# schematic.net
KiCad netlist of a schematic drawn in Altium Designer
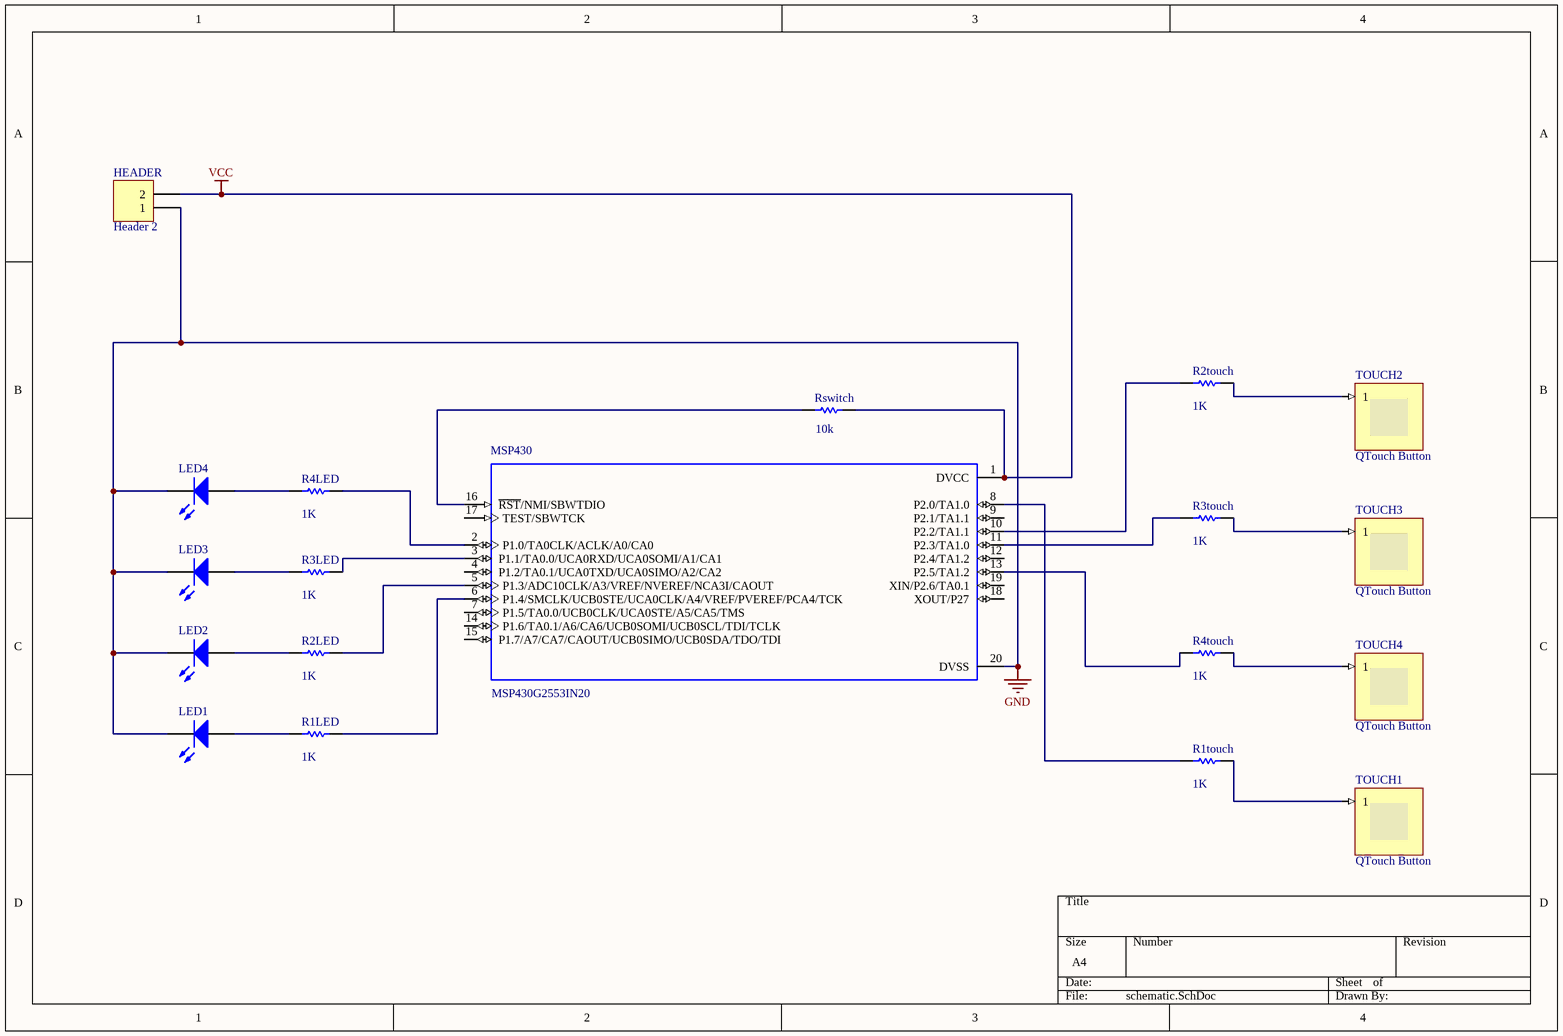
[diagram p0: schematic.SchDoc]

(export (version "E")
  (design (tool "Eeschema 10.0.6"))
  (components
    (comp (ref "HEADER")
      (value "Header 2")
      (footprint "HDR1X2")
      (description "Header, 2-Pin")
      (fields (field (name "PUBLISHER") "Altium Limited"))
      (libsource (lib "Miscellaneous Connectors") (part "Header 2"))
    )
    (comp (ref "LED1")
      (value "LED4")
      (footprint "LED-0")
      (description "Typical INFRARED GaAs LED")
      (fields (field (name "PUBLISHER") "Altium Limited"))
      (libsource (lib "Miscellaneous Devices") (part "LED0"))
    )
    (comp (ref "LED2")
      (value "LED3")
      (footprint "LED-0")
      (description "Typical INFRARED GaAs LED")
      (fields (field (name "PUBLISHER") "Altium Limited"))
      (libsource (lib "Miscellaneous Devices") (part "LED0"))
    )
    (comp (ref "LED3")
      (value "LED2")
      (footprint "LED-0")
      (description "Typical INFRARED GaAs LED")
      (fields (field (name "PUBLISHER") "Altium Limited"))
      (libsource (lib "Miscellaneous Devices") (part "LED0"))
    )
    (comp (ref "LED4")
      (value "LED1")
      (footprint "LED-0")
      (description "Typical INFRARED GaAs LED")
      (fields (field (name "PUBLISHER") "Altium Limited"))
      (libsource (lib "Miscellaneous Devices") (part "LED0"))
    )
    (comp (ref "MSP430")
      (value "MSP430G2553IN20")
      (footprint "*DIP794W45P254L2692H508Q20")
      (description "MSP430G2x53, MSP430G2x13 Mixed Signal Microcontroller 20-PDIP -40 to 85")
      (fields (field (name "MF") "Texas Instruments"))
      (libsource (lib "MSP430G2553IN20") (part "MSP430G2553IN20"))
    )
    (comp (ref "R1LED")
      (value "1K")
      (footprint "AXIAL-0.3")
      (description "Resistor")
      (fields (field (name "Comment") "Res1") (field (name "PUBLISHER") "Altium Limited"))
      (libsource (lib "Miscellaneous Devices") (part "Res1"))
    )
    (comp (ref "R1touch")
      (value "1K")
      (footprint "AXIAL-0.3")
      (description "Resistor")
      (fields (field (name "Comment") "Res1") (field (name "PUBLISHER") "Altium Limited"))
      (libsource (lib "Miscellaneous Devices") (part "Res1"))
    )
    (comp (ref "R2LED")
      (value "1K")
      (footprint "AXIAL-0.3")
      (description "Resistor")
      (fields (field (name "Comment") "Res1") (field (name "PUBLISHER") "Altium Limited"))
      (libsource (lib "Miscellaneous Devices") (part "Res1"))
    )
    (comp (ref "R2touch")
      (value "1K")
      (footprint "AXIAL-0.3")
      (description "Resistor")
      (fields (field (name "Comment") "Res1") (field (name "PUBLISHER") "Altium Limited"))
      (libsource (lib "Miscellaneous Devices") (part "Res1"))
    )
    (comp (ref "R3LED")
      (value "1K")
      (footprint "AXIAL-0.3")
      (description "Resistor")
      (fields (field (name "Comment") "Res1") (field (name "PUBLISHER") "Altium Limited"))
      (libsource (lib "Miscellaneous Devices") (part "Res1"))
    )
    (comp (ref "R3touch")
      (value "1K")
      (footprint "AXIAL-0.3")
      (description "Resistor")
      (fields (field (name "Comment") "Res1") (field (name "PUBLISHER") "Altium Limited"))
      (libsource (lib "Miscellaneous Devices") (part "Res1"))
    )
    (comp (ref "R4LED")
      (value "1K")
      (footprint "AXIAL-0.3")
      (description "Resistor")
      (fields (field (name "Comment") "Res1") (field (name "PUBLISHER") "Altium Limited"))
      (libsource (lib "Miscellaneous Devices") (part "Res1"))
    )
    (comp (ref "R4touch")
      (value "1K")
      (footprint "AXIAL-0.3")
      (description "Resistor")
      (fields (field (name "Comment") "Res1") (field (name "PUBLISHER") "Altium Limited"))
      (libsource (lib "Miscellaneous Devices") (part "Res1"))
    )
    (comp (ref "Rswitch")
      (value "10k")
      (footprint "AXIAL-0.3")
      (description "Resistor")
      (fields (field (name "Comment") "Rswitch") (field (name "PUBLISHER") "Altium Limited"))
      (libsource (lib "Miscellaneous Devices") (part "Res1"))
    )
    (comp (ref "TOUCH1") (value "QTouch Button") (libsource (lib "Atmel QTouch") (part "QTouchButton")))
    (comp (ref "TOUCH2") (value "QTouch Button") (libsource (lib "Atmel QTouch") (part "QTouchButton")))
    (comp (ref "TOUCH3") (value "QTouch Button") (libsource (lib "Atmel QTouch") (part "QTouchButton")))
    (comp (ref "TOUCH4") (value "QTouch Button") (libsource (lib "Atmel QTouch") (part "QTouchButton")))
  )
  (nets
    (net (code "1") (name "GND") (class "Default")
      (node (ref "HEADER") (pin "1") (pinfunction "1_1") (pintype "passive"))
      (node (ref "LED1") (pin "2") (pinfunction "K_2") (pintype "passive"))
      (node (ref "LED2") (pin "2") (pinfunction "K_2") (pintype "passive"))
      (node (ref "LED3") (pin "2") (pinfunction "K_2") (pintype "passive"))
      (node (ref "LED4") (pin "2") (pinfunction "K_2") (pintype "passive"))
      (node (ref "MSP430") (pin "20") (pinfunction "DVSS_20") (pintype "power_in"))
    )
    (net (code "2") (name "Net-(LED1-A)") (class "Default")
      (node (ref "LED1") (pin "1") (pinfunction "A_1") (pintype "passive"))
      (node (ref "R1LED") (pin "1") (pinfunction "1_1") (pintype "passive"))
    )
    (net (code "3") (name "Net-(LED2-A)") (class "Default")
      (node (ref "LED2") (pin "1") (pinfunction "A_1") (pintype "passive"))
      (node (ref "R2LED") (pin "1") (pinfunction "1_1") (pintype "passive"))
    )
    (net (code "4") (name "Net-(LED3-A)") (class "Default")
      (node (ref "LED3") (pin "1") (pinfunction "A_1") (pintype "passive"))
      (node (ref "R3LED") (pin "1") (pinfunction "1_1") (pintype "passive"))
    )
    (net (code "5") (name "Net-(LED4-A)") (class "Default")
      (node (ref "LED4") (pin "1") (pinfunction "A_1") (pintype "passive"))
      (node (ref "R4LED") (pin "1") (pinfunction "1_1") (pintype "passive"))
    )
    (net (code "6") (name "Net-(MSP430-P1.0{slash}TA0CLK{slash}ACLK{slash}A0{slash}CA0)") (class "Default")
      (node (ref "MSP430") (pin "2") (pinfunction "P1.0/TA0CLK/ACLK/A0/CA0_2") (pintype "bidirectional"))
      (node (ref "R4LED") (pin "2") (pinfunction "2_2") (pintype "passive"))
    )
    (net (code "7") (name "Net-(MSP430-P1.1{slash}TA0.0{slash}UCA0RXD{slash}UCA0SOMI{slash}A1{slash}CA1)") (class "Default")
      (node (ref "MSP430") (pin "3") (pinfunction "P1.1/TA0.0/UCA0RXD/UCA0SOMI/A1/CA1_3") (pintype "bidirectional"))
      (node (ref "R3LED") (pin "2") (pinfunction "2_2") (pintype "passive"))
    )
    (net (code "8") (name "Net-(MSP430-P1.3{slash}ADC10CLK{slash}A3{slash}VREF{slash}NVEREF{slash}NCA3I{slash}CAOUT)") (class "Default")
      (node (ref "MSP430") (pin "5") (pinfunction "P1.3/ADC10CLK/A3/VREF/NVEREF/NCA3I/CAOUT_5") (pintype "bidirectional"))
      (node (ref "R2LED") (pin "2") (pinfunction "2_2") (pintype "passive"))
    )
    (net (code "9") (name "Net-(MSP430-P1.4{slash}SMCLK{slash}UCB0STE{slash}UCA0CLK{slash}A4{slash}VREF{slash}PVEREF{slash}PCA4{slash}TCK)") (class "Default")
      (node (ref "MSP430") (pin "6") (pinfunction "P1.4/SMCLK/UCB0STE/UCA0CLK/A4/VREF/PVEREF/PCA4/TCK_6") (pintype "bidirectional"))
      (node (ref "R1LED") (pin "2") (pinfunction "2_2") (pintype "passive"))
    )
    (net (code "10") (name "Net-(MSP430-P2.0{slash}TA1.0)") (class "Default")
      (node (ref "MSP430") (pin "8") (pinfunction "P2.0/TA1.0_8") (pintype "bidirectional"))
      (node (ref "R1touch") (pin "1") (pinfunction "1_1") (pintype "passive"))
    )
    (net (code "11") (name "Net-(MSP430-P2.2{slash}TA1.1)") (class "Default")
      (node (ref "MSP430") (pin "10") (pinfunction "P2.2/TA1.1_10") (pintype "bidirectional"))
      (node (ref "R2touch") (pin "1") (pinfunction "1_1") (pintype "passive"))
    )
    (net (code "12") (name "Net-(MSP430-P2.3{slash}TA1.0)") (class "Default")
      (node (ref "MSP430") (pin "11") (pinfunction "P2.3/TA1.0_11") (pintype "bidirectional"))
      (node (ref "R3touch") (pin "1") (pinfunction "1_1") (pintype "passive"))
    )
    (net (code "13") (name "Net-(MSP430-P2.5{slash}TA1.2)") (class "Default")
      (node (ref "MSP430") (pin "13") (pinfunction "P2.5/TA1.2_13") (pintype "bidirectional"))
      (node (ref "R4touch") (pin "1") (pinfunction "1_1") (pintype "passive"))
    )
    (net (code "14") (name "Net-(MSP430-~{RST}{slash}NMI{slash}SBWTDIO)") (class "Default")
      (node (ref "MSP430") (pin "16") (pinfunction "~{RST}/NMI/SBWTDIO_16") (pintype "input"))
      (node (ref "Rswitch") (pin "1") (pinfunction "1_1") (pintype "passive"))
    )
    (net (code "15") (name "Net-(R1touch-Pad2)") (class "Default")
      (node (ref "R1touch") (pin "2") (pinfunction "2_2") (pintype "passive"))
      (node (ref "TOUCH1") (pin "1") (pinfunction "1_1") (pintype "input"))
    )
    (net (code "16") (name "Net-(R2touch-Pad2)") (class "Default")
      (node (ref "R2touch") (pin "2") (pinfunction "2_2") (pintype "passive"))
      (node (ref "TOUCH2") (pin "1") (pinfunction "1_1") (pintype "input"))
    )
    (net (code "17") (name "Net-(R3touch-Pad2)") (class "Default")
      (node (ref "R3touch") (pin "2") (pinfunction "2_2") (pintype "passive"))
      (node (ref "TOUCH3") (pin "1") (pinfunction "1_1") (pintype "input"))
    )
    (net (code "18") (name "Net-(R4touch-Pad2)") (class "Default")
      (node (ref "R4touch") (pin "2") (pinfunction "2_2") (pintype "passive"))
      (node (ref "TOUCH4") (pin "1") (pinfunction "1_1") (pintype "input"))
    )
    (net (code "19") (name "VCC") (class "Default")
      (node (ref "HEADER") (pin "2") (pinfunction "2_2") (pintype "passive"))
      (node (ref "MSP430") (pin "1") (pinfunction "DVCC_1") (pintype "power_in"))
      (node (ref "Rswitch") (pin "2") (pinfunction "2_2") (pintype "passive"))
    )
    (net (code "20") (name "unconnected-(MSP430-P1.2{slash}TA0.1{slash}UCA0TXD{slash}UCA0SIMO{slash}A2{slash}CA2-Pad4)") (class "Default")
      (node (ref "MSP430") (pin "4") (pinfunction "P1.2/TA0.1/UCA0TXD/UCA0SIMO/A2/CA2_4") (pintype "bidirectional"))
    )
    (net (code "21") (name "unconnected-(MSP430-P1.5{slash}TA0.0{slash}UCB0CLK{slash}UCA0STE{slash}A5{slash}CA5{slash}TMS-Pad7)") (class "Default")
      (node (ref "MSP430") (pin "7") (pinfunction "P1.5/TA0.0/UCB0CLK/UCA0STE/A5/CA5/TMS_7") (pintype "bidirectional"))
    )
    (net (code "22") (name "unconnected-(MSP430-P1.6{slash}TA0.1{slash}A6{slash}CA6{slash}UCB0SOMI{slash}UCB0SCL{slash}TDI{slash}TCLK-Pad14)") (class "Default")
      (node (ref "MSP430") (pin "14") (pinfunction "P1.6/TA0.1/A6/CA6/UCB0SOMI/UCB0SCL/TDI/TCLK_14") (pintype "bidirectional"))
    )
    (net (code "23") (name "unconnected-(MSP430-P1.7{slash}A7{slash}CA7{slash}CAOUT{slash}UCB0SIMO{slash}UCB0SDA{slash}TDO{slash}TDI-Pad15)") (class "Default")
      (node (ref "MSP430") (pin "15") (pinfunction "P1.7/A7/CA7/CAOUT/UCB0SIMO/UCB0SDA/TDO/TDI_15") (pintype "bidirectional"))
    )
    (net (code "24") (name "unconnected-(MSP430-P2.1{slash}TA1.1-Pad9)") (class "Default")
      (node (ref "MSP430") (pin "9") (pinfunction "P2.1/TA1.1_9") (pintype "bidirectional"))
    )
    (net (code "25") (name "unconnected-(MSP430-P2.4{slash}TA1.2-Pad12)") (class "Default")
      (node (ref "MSP430") (pin "12") (pinfunction "P2.4/TA1.2_12") (pintype "bidirectional"))
    )
    (net (code "26") (name "unconnected-(MSP430-TEST{slash}SBWTCK-Pad17)") (class "Default")
      (node (ref "MSP430") (pin "17") (pinfunction "TEST/SBWTCK_17") (pintype "input"))
    )
    (net (code "27") (name "unconnected-(MSP430-XIN{slash}P2.6{slash}TA0.1-Pad19)") (class "Default")
      (node (ref "MSP430") (pin "19") (pinfunction "XIN/P2.6/TA0.1_19") (pintype "bidirectional"))
    )
    (net (code "28") (name "unconnected-(MSP430-XOUT{slash}P27-Pad18)") (class "Default")
      (node (ref "MSP430") (pin "18") (pinfunction "XOUT/P27_18") (pintype "bidirectional"))
    )
  )
)
